# CPU_EX.net
KiCad netlist of a schematic drawn in Altium Designer
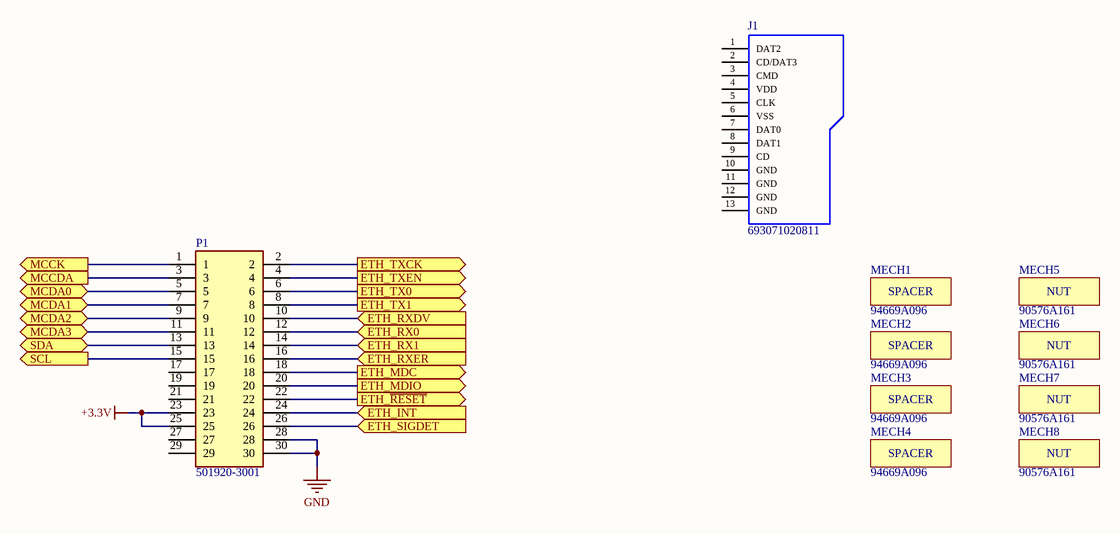
[diagram p0: CPU_EX.SchDoc]

(export (version "E")
  (design (tool "Eeschema 10.0.6"))
  (components
    (comp (ref "J1")
      (value "693071020811")
      (footprint "693071020811")
      (description "WR-CRD Micro SD Card Connector Push & Push")
      (fields (field (name "PUBLISHER") "Wurth Elektronik"))
      (libsource (lib "ModularPayload") (part "693071020811"))
    )
    (comp (ref "MECH1")
      (value "94669A096")
      (footprint "94669A096")
      (libsource (lib "ModularPayload") (part "94669A096"))
    )
    (comp (ref "MECH2")
      (value "94669A096")
      (footprint "94669A096")
      (libsource (lib "ModularPayload") (part "94669A096"))
    )
    (comp (ref "MECH3")
      (value "94669A096")
      (footprint "94669A096")
      (libsource (lib "ModularPayload") (part "94669A096"))
    )
    (comp (ref "MECH4")
      (value "94669A096")
      (footprint "94669A096")
      (libsource (lib "ModularPayload") (part "94669A096"))
    )
    (comp (ref "MECH5")
      (value "90576A161")
      (footprint "90576A161")
      (libsource (lib "ModularPayload") (part "90576A161"))
    )
    (comp (ref "MECH6")
      (value "90576A161")
      (footprint "90576A161")
      (libsource (lib "ModularPayload") (part "90576A161"))
    )
    (comp (ref "MECH7")
      (value "90576A161")
      (footprint "90576A161")
      (libsource (lib "ModularPayload") (part "90576A161"))
    )
    (comp (ref "MECH8")
      (value "90576A161")
      (footprint "90576A161")
      (libsource (lib "ModularPayload") (part "90576A161"))
    )
    (comp (ref "P1")
      (value "501920-3001")
      (footprint "5019203001")
      (description "Connector")
      (libsource (lib "ModularPayload") (part "501920-3001"))
    )
  )
  (nets
    (net (code "1") (name "+3.3V") (class "Default")
      (node (ref "P1") (pin "23") (pinfunction "23_23") (pintype "passive"))
      (node (ref "P1") (pin "25") (pinfunction "25_25") (pintype "passive"))
    )
    (net (code "2") (name "/ETH_INT") (class "Default")
      (node (ref "P1") (pin "24") (pinfunction "24_24") (pintype "passive"))
    )
    (net (code "3") (name "/ETH_MDC") (class "Default")
      (node (ref "P1") (pin "18") (pinfunction "18_18") (pintype "passive"))
    )
    (net (code "4") (name "/ETH_MDIO") (class "Default")
      (node (ref "P1") (pin "20") (pinfunction "20_20") (pintype "passive"))
    )
    (net (code "5") (name "/ETH_RX0") (class "Default")
      (node (ref "P1") (pin "12") (pinfunction "12_12") (pintype "passive"))
    )
    (net (code "6") (name "/ETH_RX1") (class "Default")
      (node (ref "P1") (pin "14") (pinfunction "14_14") (pintype "passive"))
    )
    (net (code "7") (name "/ETH_RXDV") (class "Default")
      (node (ref "P1") (pin "10") (pinfunction "10_10") (pintype "passive"))
    )
    (net (code "8") (name "/ETH_RXER") (class "Default")
      (node (ref "P1") (pin "16") (pinfunction "16_16") (pintype "passive"))
    )
    (net (code "9") (name "/ETH_SIGDET") (class "Default")
      (node (ref "P1") (pin "26") (pinfunction "26_26") (pintype "passive"))
    )
    (net (code "10") (name "/ETH_TX0") (class "Default")
      (node (ref "P1") (pin "6") (pinfunction "6_6") (pintype "passive"))
    )
    (net (code "11") (name "/ETH_TX1") (class "Default")
      (node (ref "P1") (pin "8") (pinfunction "8_8") (pintype "passive"))
    )
    (net (code "12") (name "/ETH_TXCK") (class "Default")
      (node (ref "P1") (pin "2") (pinfunction "2_2") (pintype "passive"))
    )
    (net (code "13") (name "/ETH_TXEN") (class "Default")
      (node (ref "P1") (pin "4") (pinfunction "4_4") (pintype "passive"))
    )
    (net (code "14") (name "/ETH_~{RESET}") (class "Default")
      (node (ref "P1") (pin "22") (pinfunction "22_22") (pintype "passive"))
    )
    (net (code "15") (name "/MCCDA") (class "Default")
      (node (ref "P1") (pin "3") (pinfunction "3_3") (pintype "passive"))
    )
    (net (code "16") (name "/MCCK") (class "Default")
      (node (ref "P1") (pin "1") (pinfunction "1_1") (pintype "passive"))
    )
    (net (code "17") (name "/MCDA0") (class "Default")
      (node (ref "P1") (pin "5") (pinfunction "5_5") (pintype "passive"))
    )
    (net (code "18") (name "/MCDA1") (class "Default")
      (node (ref "P1") (pin "7") (pinfunction "7_7") (pintype "passive"))
    )
    (net (code "19") (name "/MCDA2") (class "Default")
      (node (ref "P1") (pin "9") (pinfunction "9_9") (pintype "passive"))
    )
    (net (code "20") (name "/MCDA3") (class "Default")
      (node (ref "P1") (pin "11") (pinfunction "11_11") (pintype "passive"))
    )
    (net (code "21") (name "/SCL") (class "Default")
      (node (ref "P1") (pin "15") (pinfunction "15_15") (pintype "passive"))
    )
    (net (code "22") (name "/SDA") (class "Default")
      (node (ref "P1") (pin "13") (pinfunction "13_13") (pintype "passive"))
    )
    (net (code "23") (name "GND") (class "Default")
      (node (ref "P1") (pin "28") (pinfunction "28_28") (pintype "passive"))
      (node (ref "P1") (pin "30") (pinfunction "30_30") (pintype "passive"))
    )
    (net (code "24") (name "unconnected-(J1-CD-Pad9)") (class "Default")
      (node (ref "J1") (pin "9") (pinfunction "CD_9") (pintype "passive"))
    )
    (net (code "25") (name "unconnected-(J1-CD{slash}DAT3-Pad2)") (class "Default")
      (node (ref "J1") (pin "2") (pinfunction "CD/DAT3_2") (pintype "passive"))
    )
    (net (code "26") (name "unconnected-(J1-CLK-Pad5)") (class "Default")
      (node (ref "J1") (pin "5") (pinfunction "CLK_5") (pintype "passive"))
    )
    (net (code "27") (name "unconnected-(J1-CMD-Pad3)") (class "Default")
      (node (ref "J1") (pin "3") (pinfunction "CMD_3") (pintype "passive"))
    )
    (net (code "28") (name "unconnected-(J1-DAT0-Pad7)") (class "Default")
      (node (ref "J1") (pin "7") (pinfunction "DAT0_7") (pintype "passive"))
    )
    (net (code "29") (name "unconnected-(J1-DAT1-Pad8)") (class "Default")
      (node (ref "J1") (pin "8") (pinfunction "DAT1_8") (pintype "passive"))
    )
    (net (code "30") (name "unconnected-(J1-DAT2-Pad1)") (class "Default")
      (node (ref "J1") (pin "1") (pinfunction "DAT2_1") (pintype "passive"))
    )
    (net (code "31") (name "unconnected-(J1-GND-Pad10)") (class "Default")
      (node (ref "J1") (pin "10") (pinfunction "GND_10") (pintype "passive"))
    )
    (net (code "32") (name "unconnected-(J1-GND-Pad11)") (class "Default")
      (node (ref "J1") (pin "11") (pinfunction "GND_11") (pintype "passive"))
    )
    (net (code "33") (name "unconnected-(J1-GND-Pad12)") (class "Default")
      (node (ref "J1") (pin "12") (pinfunction "GND_12") (pintype "passive"))
    )
    (net (code "34") (name "unconnected-(J1-GND-Pad13)") (class "Default")
      (node (ref "J1") (pin "13") (pinfunction "GND_13") (pintype "passive"))
    )
    (net (code "35") (name "unconnected-(J1-VDD-Pad4)") (class "Default")
      (node (ref "J1") (pin "4") (pinfunction "VDD_4") (pintype "passive"))
    )
    (net (code "36") (name "unconnected-(J1-VSS-Pad6)") (class "Default")
      (node (ref "J1") (pin "6") (pinfunction "VSS_6") (pintype "passive"))
    )
    (net (code "37") (name "unconnected-(P1-Pad17)") (class "Default")
      (node (ref "P1") (pin "17") (pinfunction "17_17") (pintype "passive"))
    )
    (net (code "38") (name "unconnected-(P1-Pad19)") (class "Default")
      (node (ref "P1") (pin "19") (pinfunction "19_19") (pintype "passive"))
    )
    (net (code "39") (name "unconnected-(P1-Pad21)") (class "Default")
      (node (ref "P1") (pin "21") (pinfunction "21_21") (pintype "passive"))
    )
    (net (code "40") (name "unconnected-(P1-Pad27)") (class "Default")
      (node (ref "P1") (pin "27") (pinfunction "27_27") (pintype "passive"))
    )
    (net (code "41") (name "unconnected-(P1-Pad29)") (class "Default")
      (node (ref "P1") (pin "29") (pinfunction "29_29") (pintype "passive"))
    )
  )
)
